# multi_sensor_board_TSL230RD_TCS3200RD.net
KiCad netlist of a schematic drawn in EAGLE
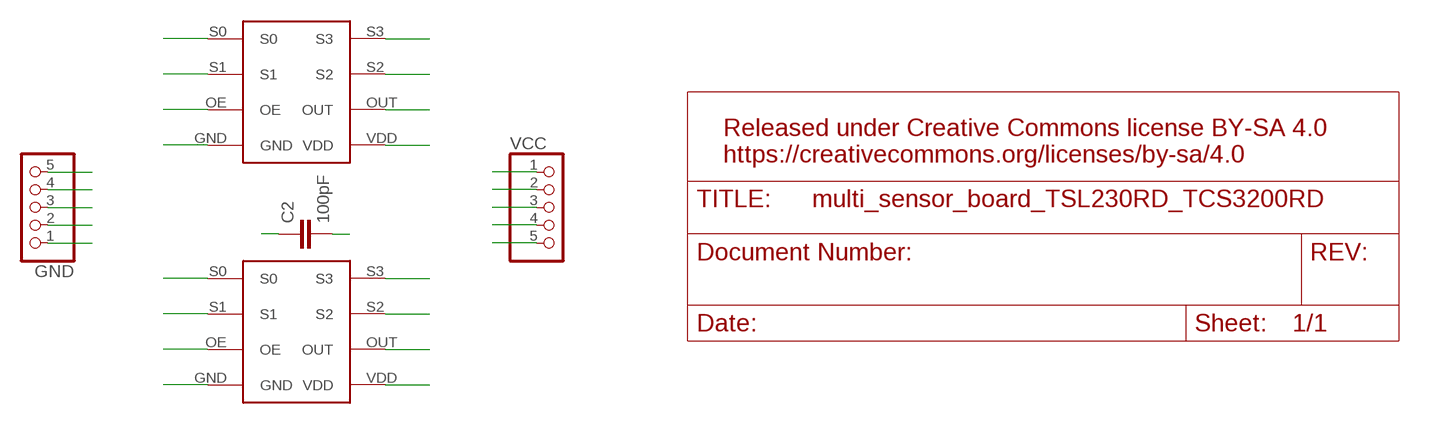
[diagram p0: schematic, sheet 1]

(export (version "E")
  (design (tool "Eeschema 10.0.6"))
  (components
    (comp (ref "C2")
      (value "100pF")
      (footprint "eagle-import:0805")
      (libsource (lib "eagle-import") (part "1.0UF-25V-+80/-20(0805)"))
    )
    (comp (ref "COLOR")
      (value "TCS3200RD")
      (footprint "eagle-import:TSL230RD")
      (libsource (lib "eagle-import") (part "TSL230RDSMD"))
    )
    (comp (ref "GND")
      (value "PINHD-1X5")
      (footprint "eagle-import:1X05")
      (libsource (lib "eagle-import") (part "PINHD-1X5"))
    )
    (comp (ref "IR")
      (value "TSL230R")
      (footprint "eagle-import:TSL230RD")
      (libsource (lib "eagle-import") (part "TSL230RDSMD"))
    )
    (comp (ref "VCC")
      (value "PINHD-1X5")
      (footprint "eagle-import:1X05")
      (libsource (lib "eagle-import") (part "PINHD-1X5"))
    )
  )
  (nets
    (net (code "1") (name "/230-OE") (class "Default")
      (node (ref "IR") (pin "OE") (pinfunction "OE_OE") (pintype "bidirectional"))
      (node (ref "VCC") (pin "1") (pinfunction "1_1") (pintype "passive"))
    )
    (net (code "2") (name "/230-OUT") (class "Default")
      (node (ref "IR") (pin "OUT") (pinfunction "OUT_OUT") (pintype "bidirectional"))
      (node (ref "VCC") (pin "2") (pinfunction "2_2") (pintype "passive"))
    )
    (net (code "3") (name "/230-S0") (class "Default")
      (node (ref "GND") (pin "5") (pinfunction "5_5") (pintype "passive"))
      (node (ref "IR") (pin "S0") (pinfunction "S0_S0") (pintype "bidirectional"))
    )
    (net (code "4") (name "/230-S1") (class "Default")
      (node (ref "GND") (pin "4") (pinfunction "4_4") (pintype "passive"))
      (node (ref "IR") (pin "S1") (pinfunction "S1_S1") (pintype "bidirectional"))
    )
    (net (code "5") (name "/3200-OE") (class "Default")
      (node (ref "COLOR") (pin "OE") (pinfunction "OE_OE") (pintype "bidirectional"))
      (node (ref "GND") (pin "2") (pinfunction "2_2") (pintype "passive"))
    )
    (net (code "6") (name "/3200-OUT") (class "Default")
      (node (ref "COLOR") (pin "OUT") (pinfunction "OUT_OUT") (pintype "bidirectional"))
      (node (ref "GND") (pin "1") (pinfunction "1_1") (pintype "passive"))
    )
    (net (code "7") (name "/3200-S2") (class "Default")
      (node (ref "COLOR") (pin "S2") (pinfunction "S2_S2") (pintype "bidirectional"))
      (node (ref "VCC") (pin "5") (pinfunction "5_5") (pintype "passive"))
    )
    (net (code "8") (name "/3200-S3") (class "Default")
      (node (ref "COLOR") (pin "S3") (pinfunction "S3_S3") (pintype "bidirectional"))
      (node (ref "VCC") (pin "4") (pinfunction "4_4") (pintype "passive"))
    )
    (net (code "9") (name "/GND") (class "Default")
      (node (ref "C2") (pin "1") (pinfunction "1_1") (pintype "passive"))
      (node (ref "COLOR") (pin "GND") (pinfunction "GND_GND") (pintype "bidirectional"))
      (node (ref "COLOR") (pin "S0") (pinfunction "S0_S0") (pintype "bidirectional"))
      (node (ref "GND") (pin "3") (pinfunction "3_3") (pintype "passive"))
      (node (ref "IR") (pin "GND") (pinfunction "GND_GND") (pintype "bidirectional"))
      (node (ref "IR") (pin "S3") (pinfunction "S3_S3") (pintype "bidirectional"))
    )
    (net (code "10") (name "/VDD") (class "Default")
      (node (ref "C2") (pin "2") (pinfunction "2_2") (pintype "passive"))
      (node (ref "COLOR") (pin "S1") (pinfunction "S1_S1") (pintype "bidirectional"))
      (node (ref "COLOR") (pin "VDD") (pinfunction "VDD_VDD") (pintype "bidirectional"))
      (node (ref "IR") (pin "S2") (pinfunction "S2_S2") (pintype "bidirectional"))
      (node (ref "IR") (pin "VDD") (pinfunction "VDD_VDD") (pintype "bidirectional"))
      (node (ref "VCC") (pin "3") (pinfunction "3_3") (pintype "passive"))
    )
  )
)
